# AT26_Chuck.net
KiCad netlist of a schematic drawn in EAGLE
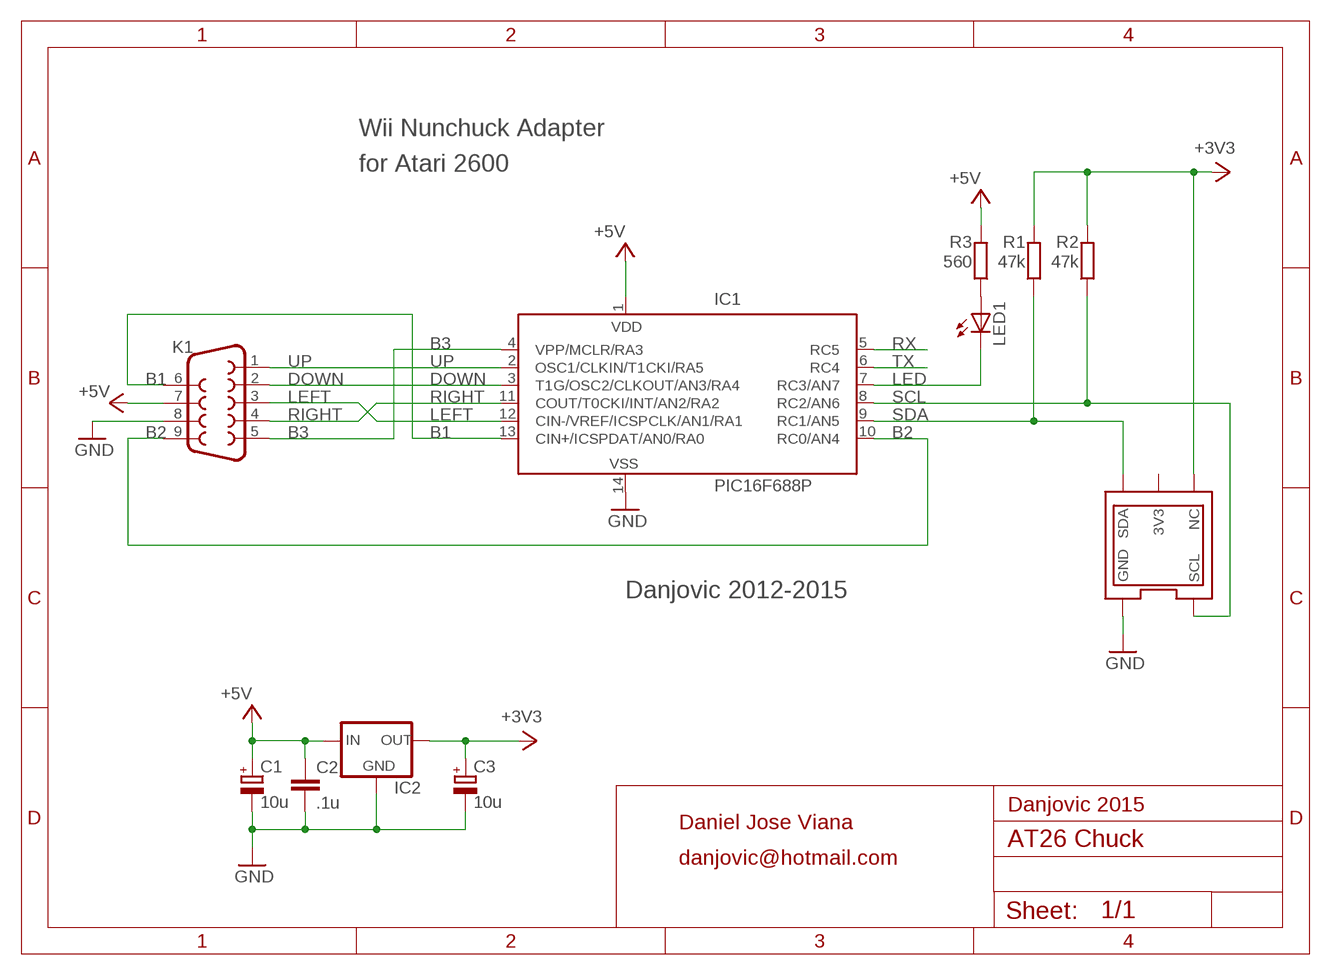
[diagram p0: schematic, sheet 1]

(export (version "E")
  (design (tool "Eeschema 10.0.6"))
  (components
    (comp (ref "C1")
      (value "10u")
      (footprint "eagle-import:E2,5-5")
      (libsource (lib "eagle-import") (part "CPOL-EUE2.5-5"))
    )
    (comp (ref "C2")
      (value ".1u")
      (footprint "eagle-import:C025-024X044L")
      (libsource (lib "eagle-import") (part "C-EU"))
    )
    (comp (ref "C3")
      (value "10u")
      (footprint "eagle-import:E2,5-5")
      (libsource (lib "eagle-import") (part "CPOL-EUE2.5-5"))
    )
    (comp (ref "IC1")
      (value "PIC16F688P")
      (footprint "eagle-import:DIL14")
      (fields (field (name "MF") "MICROCHIP") (field (name "MPN") "PIC16F676-I/P"))
      (libsource (lib "eagle-import") (part "PIC16F676P"))
    )
    (comp (ref "IC2")
      (value "78LXX78LXX_L")
      (footprint "eagle-import:78LXX_L")
      (libsource (lib "eagle-import") (part "78LXX78LXX_L"))
    )
    (comp (ref "K1")
      (value "F09D")
      (footprint "eagle-import:F09D")
      (libsource (lib "eagle-import") (part "F09D"))
    )
    (comp (ref "LED1")
      (value "LED3MM")
      (footprint "eagle-import:LED3MM")
      (libsource (lib "eagle-import") (part "LED3MM"))
    )
    (comp (ref "R1")
      (value "47k")
      (footprint "eagle-import:0204V")
      (libsource (lib "eagle-import") (part "R-EU_0204/2V"))
    )
    (comp (ref "R2")
      (value "47k")
      (footprint "eagle-import:0204V")
      (libsource (lib "eagle-import") (part "R-EU_0204/2V"))
    )
    (comp (ref "R3")
      (value "560")
      (footprint "eagle-import:0204V")
      (libsource (lib "eagle-import") (part "R-EU_0204/2V"))
    )
    (comp (ref "U$1")
      (value "NUNCHUCK")
      (footprint "eagle-import:NUNCHUCK_SLOT")
      (libsource (lib "eagle-import") (part "NUNCHUCKSLOT"))
    )
  )
  (nets
    (net (code "1") (name "+3V3") (class "Default")
      (node (ref "C3") (pin "+") (pinfunction "+_+") (pintype "passive"))
      (node (ref "IC2") (pin "OUT") (pinfunction "OUT_OUT") (pintype "passive"))
      (node (ref "R1") (pin "2") (pinfunction "2_2") (pintype "passive"))
      (node (ref "R2") (pin "2") (pinfunction "2_2") (pintype "passive"))
      (node (ref "U$1") (pin "NC") (pinfunction "NC_NC") (pintype "passive"))
    )
    (net (code "2") (name "+5V") (class "Default")
      (node (ref "C1") (pin "+") (pinfunction "+_+") (pintype "passive"))
      (node (ref "C2") (pin "1") (pinfunction "1_1") (pintype "passive"))
      (node (ref "IC1") (pin "1") (pinfunction "VDD_1") (pintype "power_in"))
      (node (ref "IC2") (pin "IN") (pinfunction "IN_IN") (pintype "input"))
      (node (ref "K1") (pin "7") (pinfunction "7_7") (pintype "passive"))
      (node (ref "R3") (pin "2") (pinfunction "2_2") (pintype "passive"))
    )
    (net (code "3") (name "/B1") (class "Default")
      (node (ref "IC1") (pin "13") (pinfunction "CIN+/ICSPDAT/AN0/RA0_13") (pintype "bidirectional"))
      (node (ref "K1") (pin "6") (pinfunction "6_6") (pintype "passive"))
    )
    (net (code "4") (name "/B2") (class "Default")
      (node (ref "IC1") (pin "10") (pinfunction "RC0/AN4_10") (pintype "bidirectional"))
      (node (ref "K1") (pin "9") (pinfunction "9_9") (pintype "passive"))
    )
    (net (code "5") (name "/B3") (class "Default")
      (node (ref "IC1") (pin "4") (pinfunction "VPP/MCLR/RA3_4") (pintype "input"))
      (node (ref "K1") (pin "5") (pinfunction "5_5") (pintype "passive"))
    )
    (net (code "6") (name "/DOWN") (class "Default")
      (node (ref "IC1") (pin "3") (pinfunction "T1G/OSC2/CLKOUT/AN3/RA4_3") (pintype "bidirectional"))
      (node (ref "K1") (pin "2") (pinfunction "2_2") (pintype "passive"))
    )
    (net (code "7") (name "/LED") (class "Default")
      (node (ref "IC1") (pin "7") (pinfunction "RC3/AN7_7") (pintype "bidirectional"))
      (node (ref "LED1") (pin "K") (pinfunction "C_K") (pintype "passive"))
    )
    (net (code "8") (name "/LEFT") (class "Default")
      (node (ref "IC1") (pin "12") (pinfunction "CIN-/VREF/ICSPCLK/AN1/RA1_12") (pintype "bidirectional"))
      (node (ref "K1") (pin "3") (pinfunction "3_3") (pintype "passive"))
    )
    (net (code "9") (name "/RIGHT") (class "Default")
      (node (ref "IC1") (pin "11") (pinfunction "COUT/T0CKI/INT/AN2/RA2_11") (pintype "bidirectional"))
      (node (ref "K1") (pin "4") (pinfunction "4_4") (pintype "passive"))
    )
    (net (code "10") (name "/RX") (class "Default")
      (node (ref "IC1") (pin "5") (pinfunction "RC5_5") (pintype "bidirectional"))
    )
    (net (code "11") (name "/SCL") (class "Default")
      (node (ref "IC1") (pin "8") (pinfunction "RC2/AN6_8") (pintype "bidirectional"))
      (node (ref "R2") (pin "1") (pinfunction "1_1") (pintype "passive"))
      (node (ref "U$1") (pin "SCL") (pinfunction "SCL_SCL") (pintype "passive"))
    )
    (net (code "12") (name "/SDA") (class "Default")
      (node (ref "IC1") (pin "9") (pinfunction "RC1/AN5_9") (pintype "bidirectional"))
      (node (ref "R1") (pin "1") (pinfunction "1_1") (pintype "passive"))
      (node (ref "U$1") (pin "SDA") (pinfunction "SDA_SDA") (pintype "bidirectional"))
    )
    (net (code "13") (name "/TX") (class "Default")
      (node (ref "IC1") (pin "6") (pinfunction "RC4_6") (pintype "bidirectional"))
    )
    (net (code "14") (name "/UP") (class "Default")
      (node (ref "IC1") (pin "2") (pinfunction "OSC1/CLKIN/T1CKI/RA5_2") (pintype "bidirectional"))
      (node (ref "K1") (pin "1") (pinfunction "1_1") (pintype "passive"))
    )
    (net (code "15") (name "GND") (class "Default")
      (node (ref "C1") (pin "-") (pinfunction "-_-") (pintype "passive"))
      (node (ref "C2") (pin "2") (pinfunction "2_2") (pintype "passive"))
      (node (ref "C3") (pin "-") (pinfunction "-_-") (pintype "passive"))
      (node (ref "IC1") (pin "14") (pinfunction "VSS_14") (pintype "power_in"))
      (node (ref "IC2") (pin "GND") (pinfunction "GND_GND") (pintype "input"))
      (node (ref "K1") (pin "8") (pinfunction "8_8") (pintype "passive"))
      (node (ref "U$1") (pin "GND") (pinfunction "GND_GND") (pintype "bidirectional"))
    )
    (net (code "16") (name "Net-(LED1-PadA)") (class "Default")
      (node (ref "LED1") (pin "A") (pinfunction "A_A") (pintype "passive"))
      (node (ref "R3") (pin "1") (pinfunction "1_1") (pintype "passive"))
    )
    (net (code "17") (name "unconnected-(U$1-Pad3V3)") (class "Default")
      (node (ref "U$1") (pin "3V3") (pinfunction "3V3_3V3") (pintype "passive"))
    )
  )
)
